# watch_new.net
KiCad netlist of a schematic drawn in EAGLE
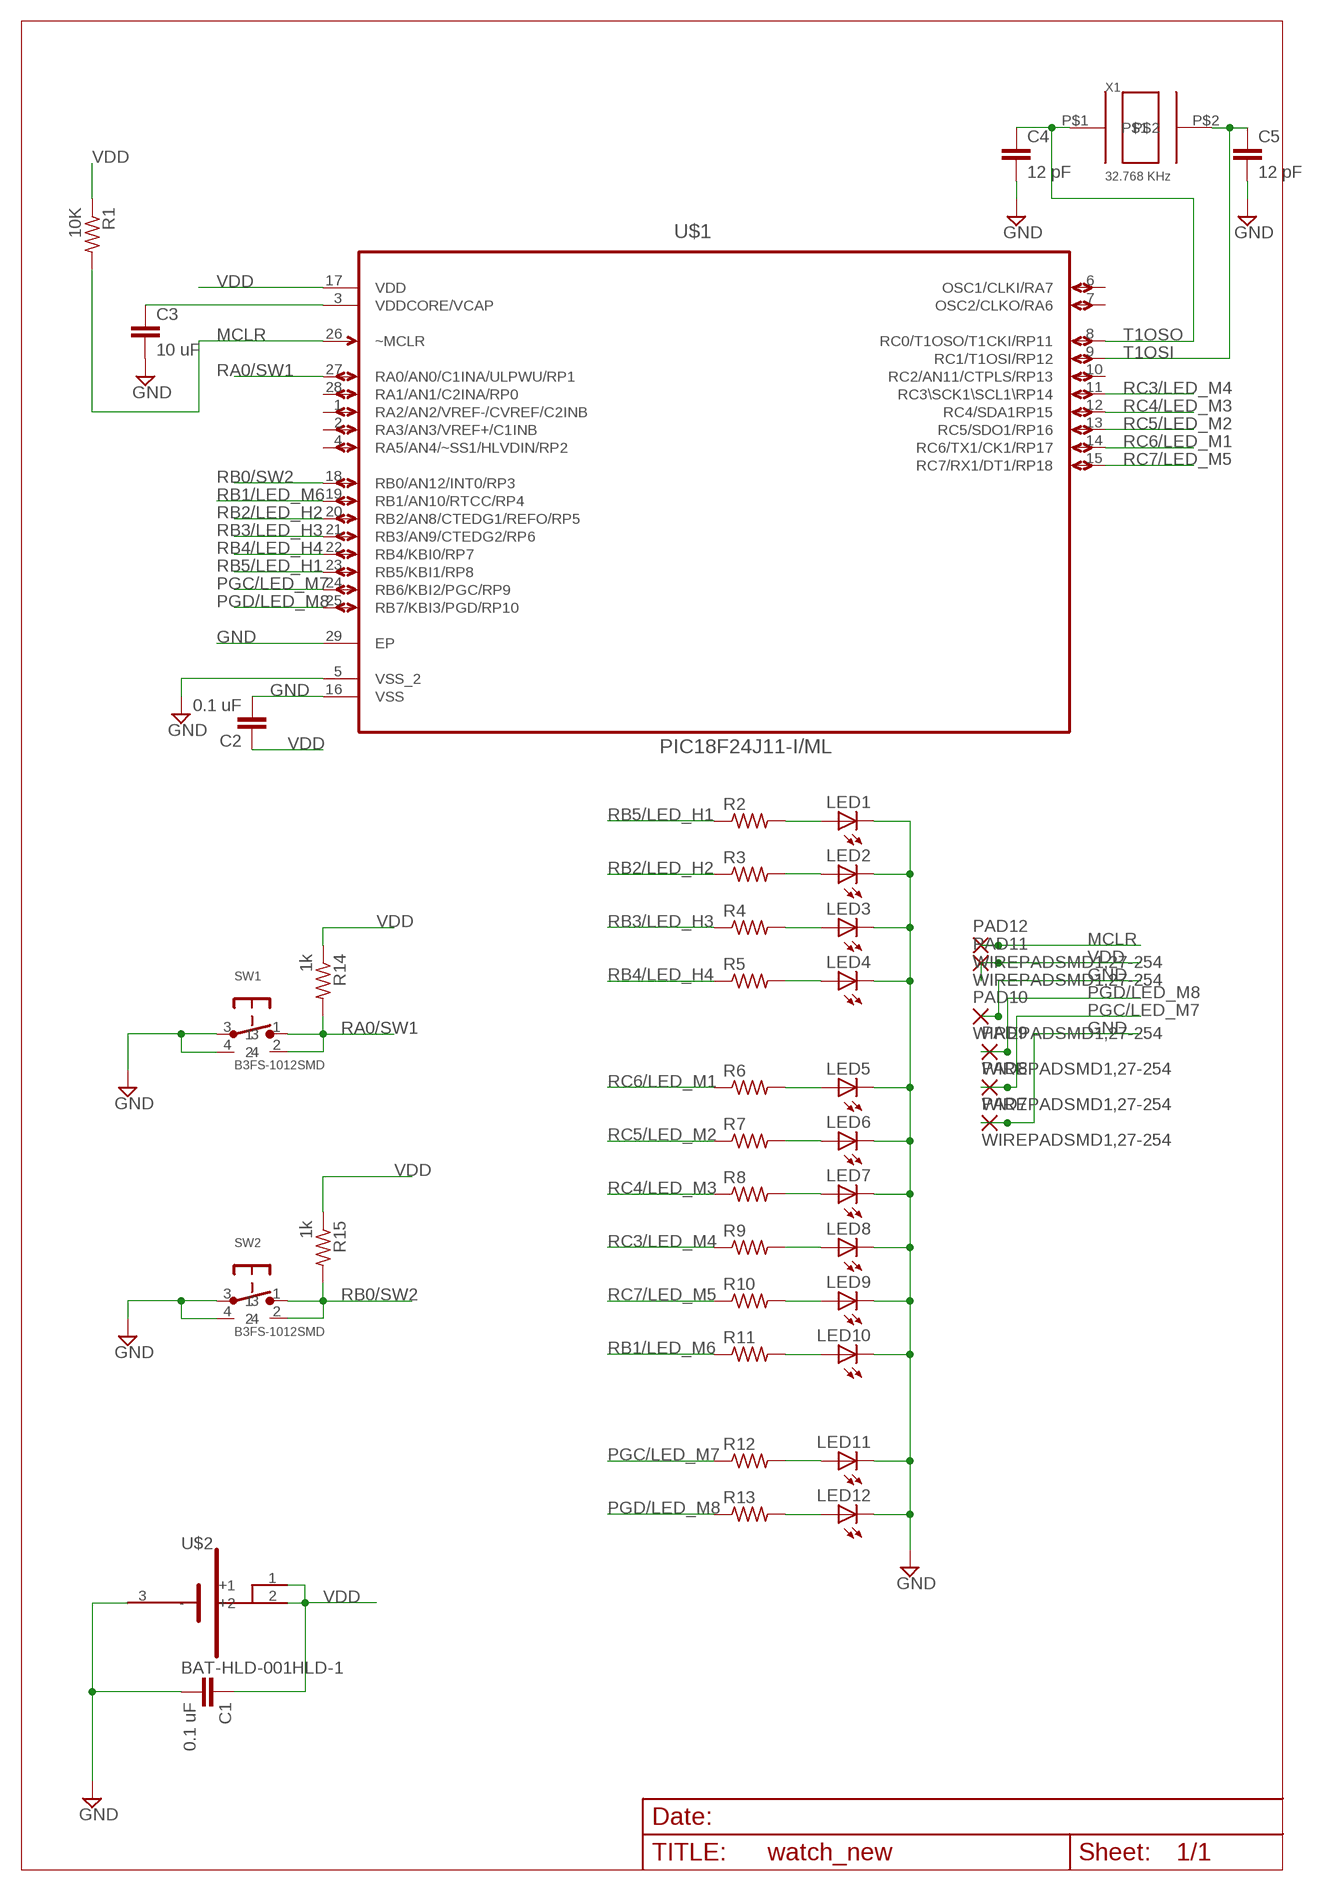
[diagram p0: schematic, sheet 1]

(export (version "E")
  (design (tool "Eeschema 10.0.6"))
  (components
    (comp (ref "C1")
      (value "0.1 uF")
      (footprint "eagle-import:C0603")
      (libsource (lib "eagle-import") (part "C-EUC0603"))
    )
    (comp (ref "C2")
      (value "0.1 uF")
      (footprint "eagle-import:C0603")
      (libsource (lib "eagle-import") (part "C-EUC0603"))
    )
    (comp (ref "C3")
      (value "10 uF")
      (footprint "eagle-import:C0603")
      (libsource (lib "eagle-import") (part "C-EUC0603"))
    )
    (comp (ref "C4")
      (value "12 pF")
      (footprint "eagle-import:C0603")
      (libsource (lib "eagle-import") (part "C-EUC0603"))
    )
    (comp (ref "C5")
      (value "12 pF")
      (footprint "eagle-import:C0603")
      (libsource (lib "eagle-import") (part "C-EUC0603"))
    )
    (comp (ref "LED1")
      (value "LEDCHIPLED_0603")
      (footprint "eagle-import:CHIPLED_0603")
      (libsource (lib "eagle-import") (part "LEDCHIPLED_0603"))
    )
    (comp (ref "LED2")
      (value "LEDCHIPLED_0603")
      (footprint "eagle-import:CHIPLED_0603")
      (libsource (lib "eagle-import") (part "LEDCHIPLED_0603"))
    )
    (comp (ref "LED3")
      (value "LEDCHIPLED_0603")
      (footprint "eagle-import:CHIPLED_0603")
      (libsource (lib "eagle-import") (part "LEDCHIPLED_0603"))
    )
    (comp (ref "LED4")
      (value "LEDCHIPLED_0603")
      (footprint "eagle-import:CHIPLED_0603")
      (libsource (lib "eagle-import") (part "LEDCHIPLED_0603"))
    )
    (comp (ref "LED5")
      (value "LEDCHIPLED_0603")
      (footprint "eagle-import:CHIPLED_0603")
      (libsource (lib "eagle-import") (part "LEDCHIPLED_0603"))
    )
    (comp (ref "LED6")
      (value "LEDCHIPLED_0603")
      (footprint "eagle-import:CHIPLED_0603")
      (libsource (lib "eagle-import") (part "LEDCHIPLED_0603"))
    )
    (comp (ref "LED7")
      (value "LEDCHIPLED_0603")
      (footprint "eagle-import:CHIPLED_0603")
      (libsource (lib "eagle-import") (part "LEDCHIPLED_0603"))
    )
    (comp (ref "LED8")
      (value "LEDCHIPLED_0603")
      (footprint "eagle-import:CHIPLED_0603")
      (libsource (lib "eagle-import") (part "LEDCHIPLED_0603"))
    )
    (comp (ref "LED9")
      (value "LEDCHIPLED_0603")
      (footprint "eagle-import:CHIPLED_0603")
      (libsource (lib "eagle-import") (part "LEDCHIPLED_0603"))
    )
    (comp (ref "LED10")
      (value "LEDCHIPLED_0603")
      (footprint "eagle-import:CHIPLED_0603")
      (libsource (lib "eagle-import") (part "LEDCHIPLED_0603"))
    )
    (comp (ref "LED11")
      (value "LEDCHIPLED_0603")
      (footprint "eagle-import:CHIPLED_0603")
      (libsource (lib "eagle-import") (part "LEDCHIPLED_0603"))
    )
    (comp (ref "LED12")
      (value "LEDCHIPLED_0603")
      (footprint "eagle-import:CHIPLED_0603")
      (libsource (lib "eagle-import") (part "LEDCHIPLED_0603"))
    )
    (comp (ref "PAD7")
      (value "WIREPADSMD1,27-254")
      (footprint "eagle-import:SMD1,27-2,54")
      (libsource (lib "eagle-import") (part "WIREPADSMD1,27-254"))
    )
    (comp (ref "PAD8")
      (value "WIREPADSMD1,27-254")
      (footprint "eagle-import:SMD1,27-2,54")
      (libsource (lib "eagle-import") (part "WIREPADSMD1,27-254"))
    )
    (comp (ref "PAD9")
      (value "WIREPADSMD1,27-254")
      (footprint "eagle-import:SMD1,27-2,54")
      (libsource (lib "eagle-import") (part "WIREPADSMD1,27-254"))
    )
    (comp (ref "PAD10")
      (value "WIREPADSMD1,27-254")
      (footprint "eagle-import:SMD1,27-2,54")
      (libsource (lib "eagle-import") (part "WIREPADSMD1,27-254"))
    )
    (comp (ref "PAD11")
      (value "WIREPADSMD1,27-254")
      (footprint "eagle-import:SMD1,27-2,54")
      (libsource (lib "eagle-import") (part "WIREPADSMD1,27-254"))
    )
    (comp (ref "PAD12")
      (value "WIREPADSMD1,27-254")
      (footprint "eagle-import:SMD1,27-2,54")
      (libsource (lib "eagle-import") (part "WIREPADSMD1,27-254"))
    )
    (comp (ref "R1")
      (value "10K")
      (footprint "eagle-import:R0603")
      (libsource (lib "eagle-import") (part "R-US_R0603"))
    )
    (comp (ref "R2")
      (value "R-US_R0603")
      (footprint "eagle-import:R0603")
      (libsource (lib "eagle-import") (part "R-US_R0603"))
    )
    (comp (ref "R3")
      (value "R-US_R0603")
      (footprint "eagle-import:R0603")
      (libsource (lib "eagle-import") (part "R-US_R0603"))
    )
    (comp (ref "R4")
      (value "R-US_R0603")
      (footprint "eagle-import:R0603")
      (libsource (lib "eagle-import") (part "R-US_R0603"))
    )
    (comp (ref "R5")
      (value "R-US_R0603")
      (footprint "eagle-import:R0603")
      (libsource (lib "eagle-import") (part "R-US_R0603"))
    )
    (comp (ref "R6")
      (value "R-US_R0603")
      (footprint "eagle-import:R0603")
      (libsource (lib "eagle-import") (part "R-US_R0603"))
    )
    (comp (ref "R7")
      (value "R-US_R0603")
      (footprint "eagle-import:R0603")
      (libsource (lib "eagle-import") (part "R-US_R0603"))
    )
    (comp (ref "R8")
      (value "R-US_R0603")
      (footprint "eagle-import:R0603")
      (libsource (lib "eagle-import") (part "R-US_R0603"))
    )
    (comp (ref "R9")
      (value "R-US_R0603")
      (footprint "eagle-import:R0603")
      (libsource (lib "eagle-import") (part "R-US_R0603"))
    )
    (comp (ref "R10")
      (value "R-US_R0603")
      (footprint "eagle-import:R0603")
      (libsource (lib "eagle-import") (part "R-US_R0603"))
    )
    (comp (ref "R11")
      (value "R-US_R0603")
      (footprint "eagle-import:R0603")
      (libsource (lib "eagle-import") (part "R-US_R0603"))
    )
    (comp (ref "R12")
      (value "R-US_R0603")
      (footprint "eagle-import:R0603")
      (libsource (lib "eagle-import") (part "R-US_R0603"))
    )
    (comp (ref "R13")
      (value "R-US_R0603")
      (footprint "eagle-import:R0603")
      (libsource (lib "eagle-import") (part "R-US_R0603"))
    )
    (comp (ref "R14")
      (value "1k")
      (footprint "eagle-import:R0603")
      (libsource (lib "eagle-import") (part "R-US_R0603"))
    )
    (comp (ref "R15")
      (value "1k")
      (footprint "eagle-import:R0603")
      (libsource (lib "eagle-import") (part "R-US_R0603"))
    )
    (comp (ref "SW1")
      (value "B3FS-1012SMD")
      (footprint "eagle-import:B3FS-1012")
      (libsource (lib "eagle-import") (part "B3FS-1012SMD"))
    )
    (comp (ref "SW2")
      (value "B3FS-1012SMD")
      (footprint "eagle-import:B3FS-1012")
      (libsource (lib "eagle-import") (part "B3FS-1012SMD"))
    )
    (comp (ref "U$1")
      (value "PIC18F24J11-I/ML")
      (footprint "eagle-import:QFN65P600X600X100-29N")
      (fields (field (name "MPN") "PIC18F24J11-I/Ml"))
      (libsource (lib "eagle-import") (part "PIC18F24J11-I/ML"))
    )
    (comp (ref "U$2")
      (value "BAT-HLD-001HLD-1")
      (footprint "eagle-import:BAT-HLD-001")
      (libsource (lib "eagle-import") (part "BAT-HLD-001HLD-1"))
    )
    (comp (ref "X1")
      (value "32.768 KHz")
      (footprint "eagle-import:XTAL_3.2X1.5")
      (libsource (lib "eagle-import") (part "ST3215SB32768E0HPWBB"))
    )
  )
  (nets
    (net (code "1") (name "/MCLR") (class "Default")
      (node (ref "PAD12") (pin "1") (pinfunction "P_1") (pintype "passive"))
      (node (ref "R1") (pin "2") (pinfunction "2_2") (pintype "passive"))
      (node (ref "U$1") (pin "26") (pinfunction "~{MCLR}_26") (pintype "input"))
    )
    (net (code "2") (name "/PGC{slash}LED_M7") (class "Default")
      (node (ref "PAD8") (pin "1") (pinfunction "P_1") (pintype "passive"))
      (node (ref "R12") (pin "1") (pinfunction "1_1") (pintype "passive"))
      (node (ref "U$1") (pin "24") (pinfunction "RB6/KBI2/PGC/RP9_24") (pintype "bidirectional"))
    )
    (net (code "3") (name "/PGD{slash}LED_M8") (class "Default")
      (node (ref "PAD9") (pin "1") (pinfunction "P_1") (pintype "passive"))
      (node (ref "R13") (pin "1") (pinfunction "1_1") (pintype "passive"))
      (node (ref "U$1") (pin "25") (pinfunction "RB7/KBI3/PGD/RP10_25") (pintype "bidirectional"))
    )
    (net (code "4") (name "/RA0{slash}SW1") (class "Default")
      (node (ref "R14") (pin "2") (pinfunction "2_2") (pintype "passive"))
      (node (ref "SW1") (pin "1") (pinfunction "1_1") (pintype "bidirectional"))
      (node (ref "SW1") (pin "2") (pinfunction "2_2") (pintype "bidirectional"))
      (node (ref "U$1") (pin "27") (pinfunction "RA0/AN0/C1INA/ULPWU/RP1_27") (pintype "bidirectional"))
    )
    (net (code "5") (name "/RB0{slash}SW2") (class "Default")
      (node (ref "R15") (pin "2") (pinfunction "2_2") (pintype "passive"))
      (node (ref "SW2") (pin "1") (pinfunction "1_1") (pintype "bidirectional"))
      (node (ref "SW2") (pin "2") (pinfunction "2_2") (pintype "bidirectional"))
      (node (ref "U$1") (pin "18") (pinfunction "RB0/AN12/INT0/RP3_18") (pintype "bidirectional"))
    )
    (net (code "6") (name "/RB1{slash}LED_M6") (class "Default")
      (node (ref "R11") (pin "1") (pinfunction "1_1") (pintype "passive"))
      (node (ref "U$1") (pin "19") (pinfunction "RB1/AN10/RTCC/RP4_19") (pintype "bidirectional"))
    )
    (net (code "7") (name "/RB2{slash}LED_H2") (class "Default")
      (node (ref "R3") (pin "1") (pinfunction "1_1") (pintype "passive"))
      (node (ref "U$1") (pin "20") (pinfunction "RB2/AN8/CTEDG1/REFO/RP5_20") (pintype "bidirectional"))
    )
    (net (code "8") (name "/RB3{slash}LED_H3") (class "Default")
      (node (ref "R4") (pin "1") (pinfunction "1_1") (pintype "passive"))
      (node (ref "U$1") (pin "21") (pinfunction "RB3/AN9/CTEDG2/RP6_21") (pintype "bidirectional"))
    )
    (net (code "9") (name "/RB4{slash}LED_H4") (class "Default")
      (node (ref "R5") (pin "1") (pinfunction "1_1") (pintype "passive"))
      (node (ref "U$1") (pin "22") (pinfunction "RB4/KBI0/RP7_22") (pintype "bidirectional"))
    )
    (net (code "10") (name "/RB5{slash}LED_H1") (class "Default")
      (node (ref "R2") (pin "1") (pinfunction "1_1") (pintype "passive"))
      (node (ref "U$1") (pin "23") (pinfunction "RB5/KBI1/RP8_23") (pintype "bidirectional"))
    )
    (net (code "11") (name "/RC3{slash}LED_M4") (class "Default")
      (node (ref "R9") (pin "1") (pinfunction "1_1") (pintype "passive"))
      (node (ref "U$1") (pin "11") (pinfunction "RC3\\SCK1\\SCL1\\RP14_11") (pintype "bidirectional"))
    )
    (net (code "12") (name "/RC4{slash}LED_M3") (class "Default")
      (node (ref "R8") (pin "1") (pinfunction "1_1") (pintype "passive"))
      (node (ref "U$1") (pin "12") (pinfunction "RC4/SDA1RP15_12") (pintype "bidirectional"))
    )
    (net (code "13") (name "/RC5{slash}LED_M2") (class "Default")
      (node (ref "R7") (pin "1") (pinfunction "1_1") (pintype "passive"))
      (node (ref "U$1") (pin "13") (pinfunction "RC5/SDO1/RP16_13") (pintype "bidirectional"))
    )
    (net (code "14") (name "/RC6{slash}LED_M1") (class "Default")
      (node (ref "R6") (pin "1") (pinfunction "1_1") (pintype "passive"))
      (node (ref "U$1") (pin "14") (pinfunction "RC6/TX1/CK1/RP17_14") (pintype "bidirectional"))
    )
    (net (code "15") (name "/RC7{slash}LED_M5") (class "Default")
      (node (ref "R10") (pin "1") (pinfunction "1_1") (pintype "passive"))
      (node (ref "U$1") (pin "15") (pinfunction "RC7/RX1/DT1/RP18_15") (pintype "bidirectional"))
    )
    (net (code "16") (name "/T1OSI") (class "Default")
      (node (ref "C5") (pin "1") (pinfunction "1_1") (pintype "passive"))
      (node (ref "U$1") (pin "9") (pinfunction "RC1/T1OSI/RP12_9") (pintype "bidirectional"))
      (node (ref "X1") (pin "P$2") (pinfunction "P$2_P$2") (pintype "bidirectional"))
    )
    (net (code "17") (name "/T1OSO") (class "Default")
      (node (ref "C4") (pin "1") (pinfunction "1_1") (pintype "passive"))
      (node (ref "U$1") (pin "8") (pinfunction "RC0/T1OSO/T1CKI/RP11_8") (pintype "bidirectional"))
      (node (ref "X1") (pin "P$1") (pinfunction "P$1_P$1") (pintype "bidirectional"))
    )
    (net (code "18") (name "/VDD") (class "Default")
      (node (ref "C1") (pin "1") (pinfunction "1_1") (pintype "passive"))
      (node (ref "C2") (pin "1") (pinfunction "1_1") (pintype "passive"))
      (node (ref "PAD11") (pin "1") (pinfunction "P_1") (pintype "passive"))
      (node (ref "R1") (pin "1") (pinfunction "1_1") (pintype "passive"))
      (node (ref "R14") (pin "1") (pinfunction "1_1") (pintype "passive"))
      (node (ref "R15") (pin "1") (pinfunction "1_1") (pintype "passive"))
      (node (ref "U$1") (pin "17") (pinfunction "VDD_17") (pintype "power_in"))
      (node (ref "U$2") (pin "1") (pinfunction "+1_1") (pintype "bidirectional"))
      (node (ref "U$2") (pin "2") (pinfunction "+2_2") (pintype "bidirectional"))
    )
    (net (code "19") (name "GND") (class "Default")
      (node (ref "C1") (pin "2") (pinfunction "2_2") (pintype "passive"))
      (node (ref "C2") (pin "2") (pinfunction "2_2") (pintype "passive"))
      (node (ref "C3") (pin "2") (pinfunction "2_2") (pintype "passive"))
      (node (ref "C4") (pin "2") (pinfunction "2_2") (pintype "passive"))
      (node (ref "C5") (pin "2") (pinfunction "2_2") (pintype "passive"))
      (node (ref "LED1") (pin "C") (pinfunction "C_C") (pintype "passive"))
      (node (ref "LED10") (pin "C") (pinfunction "C_C") (pintype "passive"))
      (node (ref "LED11") (pin "C") (pinfunction "C_C") (pintype "passive"))
      (node (ref "LED12") (pin "C") (pinfunction "C_C") (pintype "passive"))
      (node (ref "LED2") (pin "C") (pinfunction "C_C") (pintype "passive"))
      (node (ref "LED3") (pin "C") (pinfunction "C_C") (pintype "passive"))
      (node (ref "LED4") (pin "C") (pinfunction "C_C") (pintype "passive"))
      (node (ref "LED5") (pin "C") (pinfunction "C_C") (pintype "passive"))
      (node (ref "LED6") (pin "C") (pinfunction "C_C") (pintype "passive"))
      (node (ref "LED7") (pin "C") (pinfunction "C_C") (pintype "passive"))
      (node (ref "LED8") (pin "C") (pinfunction "C_C") (pintype "passive"))
      (node (ref "LED9") (pin "C") (pinfunction "C_C") (pintype "passive"))
      (node (ref "PAD10") (pin "1") (pinfunction "P_1") (pintype "passive"))
      (node (ref "PAD7") (pin "1") (pinfunction "P_1") (pintype "passive"))
      (node (ref "SW1") (pin "3") (pinfunction "3_3") (pintype "bidirectional"))
      (node (ref "SW1") (pin "4") (pinfunction "4_4") (pintype "bidirectional"))
      (node (ref "SW2") (pin "3") (pinfunction "3_3") (pintype "bidirectional"))
      (node (ref "SW2") (pin "4") (pinfunction "4_4") (pintype "bidirectional"))
      (node (ref "U$1") (pin "16") (pinfunction "VSS_16") (pintype "passive"))
      (node (ref "U$1") (pin "29") (pinfunction "EP_29") (pintype "passive"))
      (node (ref "U$1") (pin "5") (pinfunction "VSS_2_5") (pintype "passive"))
      (node (ref "U$2") (pin "3") (pinfunction "-_3") (pintype "bidirectional"))
    )
    (net (code "20") (name "Net-(LED1-PadA)") (class "Default")
      (node (ref "LED1") (pin "A") (pinfunction "A_A") (pintype "passive"))
      (node (ref "R2") (pin "2") (pinfunction "2_2") (pintype "passive"))
    )
    (net (code "21") (name "Net-(LED2-PadA)") (class "Default")
      (node (ref "LED2") (pin "A") (pinfunction "A_A") (pintype "passive"))
      (node (ref "R3") (pin "2") (pinfunction "2_2") (pintype "passive"))
    )
    (net (code "22") (name "Net-(LED3-PadA)") (class "Default")
      (node (ref "LED3") (pin "A") (pinfunction "A_A") (pintype "passive"))
      (node (ref "R4") (pin "2") (pinfunction "2_2") (pintype "passive"))
    )
    (net (code "23") (name "Net-(LED4-PadA)") (class "Default")
      (node (ref "LED4") (pin "A") (pinfunction "A_A") (pintype "passive"))
      (node (ref "R5") (pin "2") (pinfunction "2_2") (pintype "passive"))
    )
    (net (code "24") (name "Net-(LED5-PadA)") (class "Default")
      (node (ref "LED5") (pin "A") (pinfunction "A_A") (pintype "passive"))
      (node (ref "R6") (pin "2") (pinfunction "2_2") (pintype "passive"))
    )
    (net (code "25") (name "Net-(LED6-PadA)") (class "Default")
      (node (ref "LED6") (pin "A") (pinfunction "A_A") (pintype "passive"))
      (node (ref "R7") (pin "2") (pinfunction "2_2") (pintype "passive"))
    )
    (net (code "26") (name "Net-(LED7-PadA)") (class "Default")
      (node (ref "LED7") (pin "A") (pinfunction "A_A") (pintype "passive"))
      (node (ref "R8") (pin "2") (pinfunction "2_2") (pintype "passive"))
    )
    (net (code "27") (name "Net-(LED8-PadA)") (class "Default")
      (node (ref "LED8") (pin "A") (pinfunction "A_A") (pintype "passive"))
      (node (ref "R9") (pin "2") (pinfunction "2_2") (pintype "passive"))
    )
    (net (code "28") (name "Net-(LED9-PadA)") (class "Default")
      (node (ref "LED9") (pin "A") (pinfunction "A_A") (pintype "passive"))
      (node (ref "R10") (pin "2") (pinfunction "2_2") (pintype "passive"))
    )
    (net (code "29") (name "Net-(LED10-PadA)") (class "Default")
      (node (ref "LED10") (pin "A") (pinfunction "A_A") (pintype "passive"))
      (node (ref "R11") (pin "2") (pinfunction "2_2") (pintype "passive"))
    )
    (net (code "30") (name "Net-(LED11-PadA)") (class "Default")
      (node (ref "LED11") (pin "A") (pinfunction "A_A") (pintype "passive"))
      (node (ref "R12") (pin "2") (pinfunction "2_2") (pintype "passive"))
    )
    (net (code "31") (name "Net-(LED12-PadA)") (class "Default")
      (node (ref "LED12") (pin "A") (pinfunction "A_A") (pintype "passive"))
      (node (ref "R13") (pin "2") (pinfunction "2_2") (pintype "passive"))
    )
    (net (code "32") (name "Net-(U$1-VDDCORE{slash}VCAP)") (class "Default")
      (node (ref "C3") (pin "1") (pinfunction "1_1") (pintype "passive"))
      (node (ref "U$1") (pin "3") (pinfunction "VDDCORE/VCAP_3") (pintype "power_in"))
    )
    (net (code "33") (name "unconnected-(U$1-OSC1{slash}CLKI{slash}RA7-Pad6)") (class "Default")
      (node (ref "U$1") (pin "6") (pinfunction "OSC1/CLKI/RA7_6") (pintype "bidirectional"))
    )
    (net (code "34") (name "unconnected-(U$1-OSC2{slash}CLKO{slash}RA6-Pad7)") (class "Default")
      (node (ref "U$1") (pin "7") (pinfunction "OSC2/CLKO/RA6_7") (pintype "bidirectional"))
    )
    (net (code "35") (name "unconnected-(U$1-RA1{slash}AN1{slash}C2INA{slash}RP0-Pad28)") (class "Default")
      (node (ref "U$1") (pin "28") (pinfunction "RA1/AN1/C2INA/RP0_28") (pintype "bidirectional"))
    )
    (net (code "36") (name "unconnected-(U$1-RA2{slash}AN2{slash}VREF-{slash}CVREF{slash}C2INB-Pad1)") (class "Default")
      (node (ref "U$1") (pin "1") (pinfunction "RA2/AN2/VREF-/CVREF/C2INB_1") (pintype "bidirectional"))
    )
    (net (code "37") (name "unconnected-(U$1-RA3{slash}AN3{slash}VREF+{slash}C1INB-Pad2)") (class "Default")
      (node (ref "U$1") (pin "2") (pinfunction "RA3/AN3/VREF+/C1INB_2") (pintype "bidirectional"))
    )
    (net (code "38") (name "unconnected-(U$1-RA5{slash}AN4{slash}~{SS1{slash}HLVDIN{slash}RP2}-Pad4)") (class "Default")
      (node (ref "U$1") (pin "4") (pinfunction "RA5/AN4/~{SS1/HLVDIN/RP2}_4") (pintype "bidirectional"))
    )
    (net (code "39") (name "unconnected-(U$1-RC2{slash}AN11{slash}CTPLS{slash}RP13-Pad10)") (class "Default")
      (node (ref "U$1") (pin "10") (pinfunction "RC2/AN11/CTPLS/RP13_10") (pintype "bidirectional"))
    )
  )
)
